# Projeto_esquem_tico.net
KiCad netlist of a schematic drawn in EAGLE
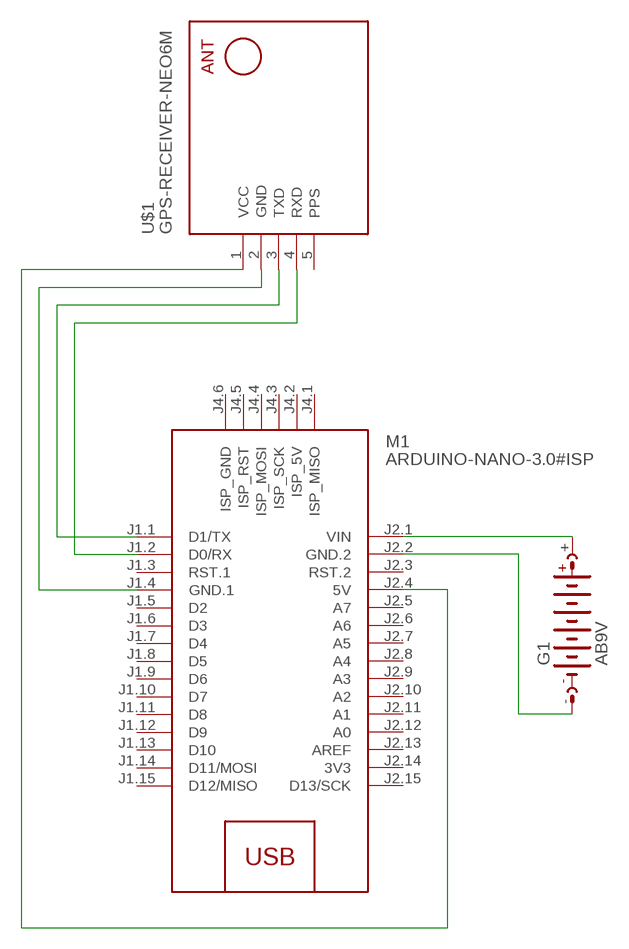
[diagram p0: schematic, sheet 1]

(export (version "E")
  (design (tool "Eeschema 10.0.6"))
  (components
    (comp (ref "G1")
      (value "AB9V")
      (footprint "eagle-import:AB9V")
      (libsource (lib "eagle-import") (part "AB9V"))
    )
    (comp (ref "M1")
      (value "ARDUINO-NANO-3.0#ISP")
      (footprint "eagle-import:ARDUINO-NANO-3.0#ISP")
      (libsource (lib "eagle-import") (part "ARDUINO-NANO-3.0#ISP"))
    )
    (comp (ref "U$1")
      (value "GPS-RECEIVER-NEO6M")
      (footprint "eagle-import:GPS-RECEIVER-NEO6M")
      (libsource (lib "eagle-import") (part "GPS-RECEIVER-NEO6M"))
    )
  )
  (nets
    (net (code "1") (name "/3V3") (class "Default")
      (node (ref "M1") (pin "J2.14") (pinfunction "3V3_J2.14") (pintype "power_in"))
    )
    (net (code "2") (name "/PPS") (class "Default")
      (node (ref "U$1") (pin "5") (pinfunction "PPS_5") (pintype "power_in"))
    )
    (net (code "3") (name "Net-(M1-5V)") (class "Default")
      (node (ref "M1") (pin "J2.4") (pinfunction "5V_J2.4") (pintype "power_in"))
      (node (ref "U$1") (pin "1") (pinfunction "VCC_1") (pintype "bidirectional"))
    )
    (net (code "4") (name "Net-(M1-D0{slash}RX)") (class "Default")
      (node (ref "M1") (pin "J1.2") (pinfunction "D0/RX_J1.2") (pintype "bidirectional"))
      (node (ref "U$1") (pin "4") (pinfunction "RXD_4") (pintype "power_in"))
    )
    (net (code "5") (name "Net-(M1-D1{slash}TX)") (class "Default")
      (node (ref "M1") (pin "J1.1") (pinfunction "D1/TX_J1.1") (pintype "bidirectional"))
      (node (ref "U$1") (pin "3") (pinfunction "TXD_3") (pintype "bidirectional"))
    )
    (net (code "6") (name "Net-(M1-GND.1)") (class "Default")
      (node (ref "M1") (pin "J1.4") (pinfunction "GND.1_J1.4") (pintype "power_in"))
      (node (ref "U$1") (pin "2") (pinfunction "GND_2") (pintype "bidirectional"))
    )
    (net (code "7") (name "Net-(M1-GND.2)") (class "Default")
      (node (ref "G1") (pin "-") (pinfunction "-_-") (pintype "passive"))
      (node (ref "M1") (pin "J2.2") (pinfunction "GND.2_J2.2") (pintype "power_in"))
    )
    (net (code "8") (name "Net-(M1-VIN)") (class "Default")
      (node (ref "G1") (pin "+") (pinfunction "+_+") (pintype "passive"))
      (node (ref "M1") (pin "J2.1") (pinfunction "VIN_J2.1") (pintype "power_in"))
    )
    (net (code "9") (name "unconnected-(M1-A0-PadJ2.12)") (class "Default")
      (node (ref "M1") (pin "J2.12") (pinfunction "A0_J2.12") (pintype "bidirectional"))
    )
    (net (code "10") (name "unconnected-(M1-A1-PadJ2.11)") (class "Default")
      (node (ref "M1") (pin "J2.11") (pinfunction "A1_J2.11") (pintype "bidirectional"))
    )
    (net (code "11") (name "unconnected-(M1-A2-PadJ2.10)") (class "Default")
      (node (ref "M1") (pin "J2.10") (pinfunction "A2_J2.10") (pintype "bidirectional"))
    )
    (net (code "12") (name "unconnected-(M1-A3-PadJ2.9)") (class "Default")
      (node (ref "M1") (pin "J2.9") (pinfunction "A3_J2.9") (pintype "bidirectional"))
    )
    (net (code "13") (name "unconnected-(M1-A4-PadJ2.8)") (class "Default")
      (node (ref "M1") (pin "J2.8") (pinfunction "A4_J2.8") (pintype "bidirectional"))
    )
    (net (code "14") (name "unconnected-(M1-A5-PadJ2.7)") (class "Default")
      (node (ref "M1") (pin "J2.7") (pinfunction "A5_J2.7") (pintype "bidirectional"))
    )
    (net (code "15") (name "unconnected-(M1-A6-PadJ2.6)") (class "Default")
      (node (ref "M1") (pin "J2.6") (pinfunction "A6_J2.6") (pintype "bidirectional"))
    )
    (net (code "16") (name "unconnected-(M1-A7-PadJ2.5)") (class "Default")
      (node (ref "M1") (pin "J2.5") (pinfunction "A7_J2.5") (pintype "bidirectional"))
    )
    (net (code "17") (name "unconnected-(M1-AREF-PadJ2.13)") (class "Default")
      (node (ref "M1") (pin "J2.13") (pinfunction "AREF_J2.13") (pintype "bidirectional"))
    )
    (net (code "18") (name "unconnected-(M1-D2-PadJ1.5)") (class "Default")
      (node (ref "M1") (pin "J1.5") (pinfunction "D2_J1.5") (pintype "bidirectional"))
    )
    (net (code "19") (name "unconnected-(M1-D3-PadJ1.6)") (class "Default")
      (node (ref "M1") (pin "J1.6") (pinfunction "D3_J1.6") (pintype "bidirectional"))
    )
    (net (code "20") (name "unconnected-(M1-D4-PadJ1.7)") (class "Default")
      (node (ref "M1") (pin "J1.7") (pinfunction "D4_J1.7") (pintype "bidirectional"))
    )
    (net (code "21") (name "unconnected-(M1-D5-PadJ1.8)") (class "Default")
      (node (ref "M1") (pin "J1.8") (pinfunction "D5_J1.8") (pintype "bidirectional"))
    )
    (net (code "22") (name "unconnected-(M1-D6-PadJ1.9)") (class "Default")
      (node (ref "M1") (pin "J1.9") (pinfunction "D6_J1.9") (pintype "bidirectional"))
    )
    (net (code "23") (name "unconnected-(M1-D7-PadJ1.10)") (class "Default")
      (node (ref "M1") (pin "J1.10") (pinfunction "D7_J1.10") (pintype "bidirectional"))
    )
    (net (code "24") (name "unconnected-(M1-D8-PadJ1.11)") (class "Default")
      (node (ref "M1") (pin "J1.11") (pinfunction "D8_J1.11") (pintype "bidirectional"))
    )
    (net (code "25") (name "unconnected-(M1-D9-PadJ1.12)") (class "Default")
      (node (ref "M1") (pin "J1.12") (pinfunction "D9_J1.12") (pintype "bidirectional"))
    )
    (net (code "26") (name "unconnected-(M1-D10-PadJ1.13)") (class "Default")
      (node (ref "M1") (pin "J1.13") (pinfunction "D10_J1.13") (pintype "bidirectional"))
    )
    (net (code "27") (name "unconnected-(M1-D11{slash}MOSI-PadJ1.14)") (class "Default")
      (node (ref "M1") (pin "J1.14") (pinfunction "D11/MOSI_J1.14") (pintype "bidirectional"))
    )
    (net (code "28") (name "unconnected-(M1-D12{slash}MISO-PadJ1.15)") (class "Default")
      (node (ref "M1") (pin "J1.15") (pinfunction "D12/MISO_J1.15") (pintype "bidirectional"))
    )
    (net (code "29") (name "unconnected-(M1-D13{slash}SCK-PadJ2.15)") (class "Default")
      (node (ref "M1") (pin "J2.15") (pinfunction "D13/SCK_J2.15") (pintype "bidirectional"))
    )
    (net (code "30") (name "unconnected-(M1-ISP_5V-PadJ4.2)") (class "Default")
      (node (ref "M1") (pin "J4.2") (pinfunction "ISP_5V_J4.2") (pintype "bidirectional"))
    )
    (net (code "31") (name "unconnected-(M1-ISP_GND-PadJ4.6)") (class "Default")
      (node (ref "M1") (pin "J4.6") (pinfunction "ISP_GND_J4.6") (pintype "bidirectional"))
    )
    (net (code "32") (name "unconnected-(M1-ISP_MISO-PadJ4.1)") (class "Default")
      (node (ref "M1") (pin "J4.1") (pinfunction "ISP_MISO_J4.1") (pintype "bidirectional"))
    )
    (net (code "33") (name "unconnected-(M1-ISP_MOSI-PadJ4.4)") (class "Default")
      (node (ref "M1") (pin "J4.4") (pinfunction "ISP_MOSI_J4.4") (pintype "bidirectional"))
    )
    (net (code "34") (name "unconnected-(M1-ISP_RST-PadJ4.5)") (class "Default")
      (node (ref "M1") (pin "J4.5") (pinfunction "ISP_RST_J4.5") (pintype "bidirectional"))
    )
    (net (code "35") (name "unconnected-(M1-ISP_SCK-PadJ4.3)") (class "Default")
      (node (ref "M1") (pin "J4.3") (pinfunction "ISP_SCK_J4.3") (pintype "bidirectional"))
    )
    (net (code "36") (name "unconnected-(M1-RST.1-PadJ1.3)") (class "Default")
      (node (ref "M1") (pin "J1.3") (pinfunction "RST.1_J1.3") (pintype "bidirectional"))
    )
    (net (code "37") (name "unconnected-(M1-RST.2-PadJ2.3)") (class "Default")
      (node (ref "M1") (pin "J2.3") (pinfunction "RST.2_J2.3") (pintype "bidirectional"))
    )
  )
)
